# 7_U-FL-Connectors_GND.net
KiCad netlist of a schematic drawn in Altium Designer
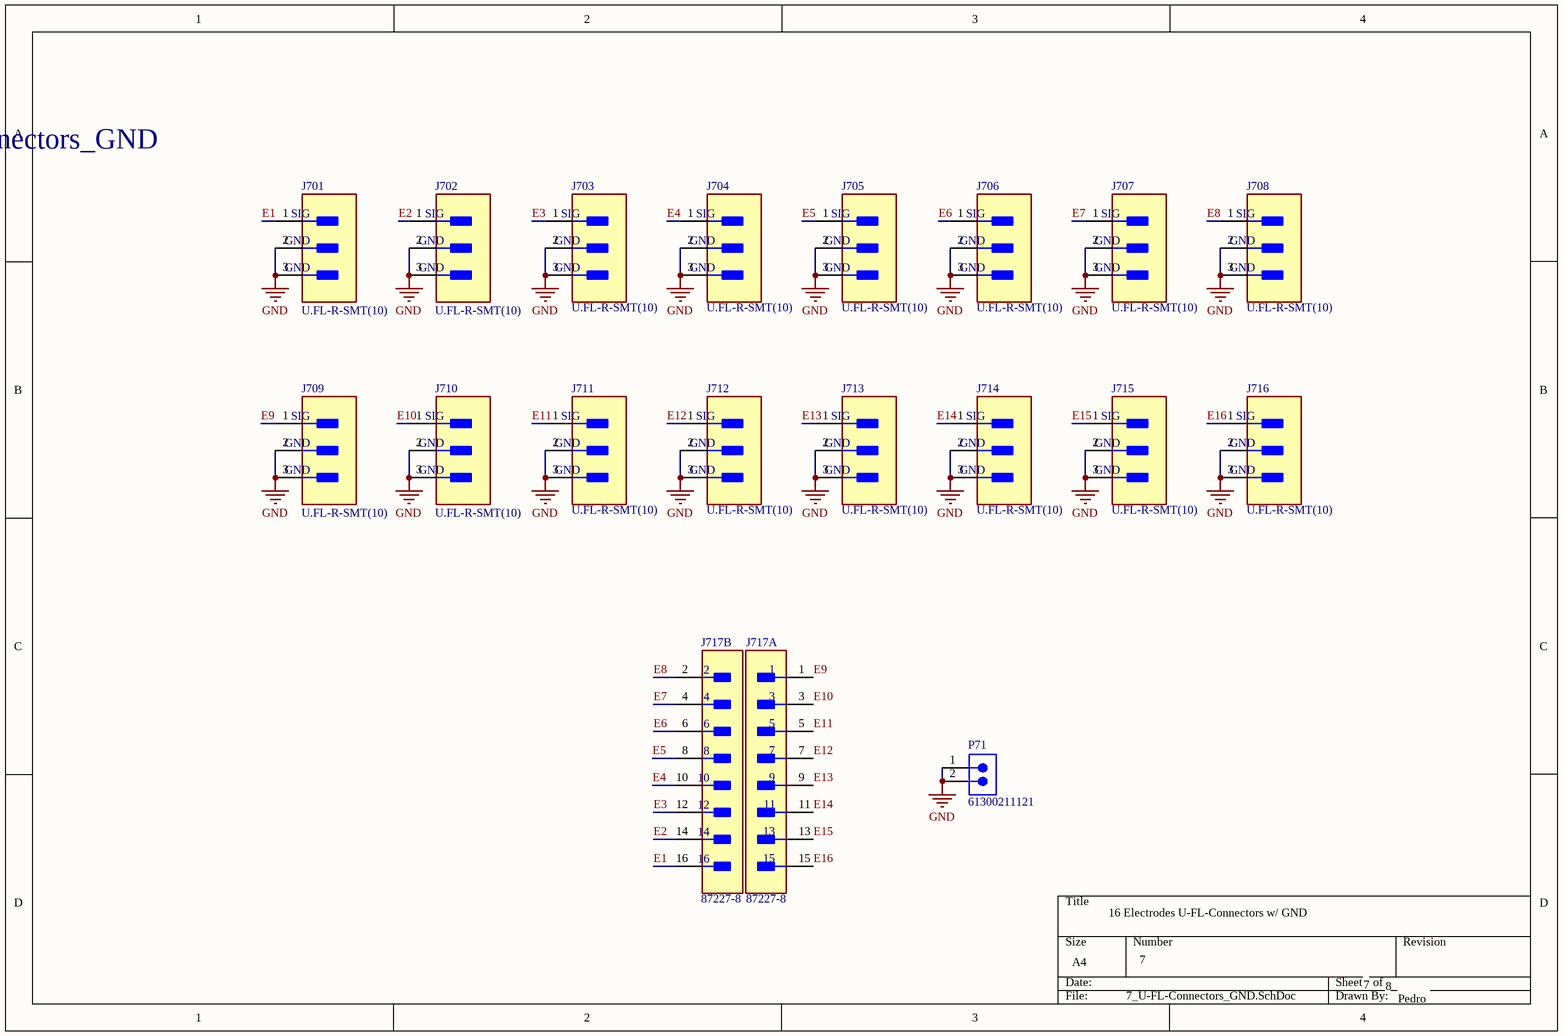
[diagram p0: 7_U-FL-Connectors_GND.SchDoc]

(export (version "E")
  (design (tool "Eeschema 10.0.6"))
  (components
    (comp (ref "J701")
      (value "U.FL-R-SMT(10)")
      (footprint "FP-U_FL-R-SMT_10-MFG")
      (description "CONN U.FL RCPT STR 50 OHM SMD")
      (libsource (lib "RPI_EIT_SchLib") (part "eef6fde44c591823e8076210edfe12f"))
    )
    (comp (ref "J702")
      (value "U.FL-R-SMT(10)")
      (footprint "FP-U_FL-R-SMT_10-MFG")
      (description "CONN U.FL RCPT STR 50 OHM SMD")
      (libsource (lib "RPI_EIT_SchLib") (part "eef6fde44c591823e8076210edfe12f"))
    )
    (comp (ref "J703")
      (value "U.FL-R-SMT(10)")
      (footprint "FP-U_FL-R-SMT_10-MFG")
      (description "CONN U.FL RCPT STR 50 OHM SMD")
      (libsource (lib "RPI_EIT_SchLib") (part "eef6fde44c591823e8076210edfe12f"))
    )
    (comp (ref "J704")
      (value "U.FL-R-SMT(10)")
      (footprint "FP-U_FL-R-SMT_10-MFG")
      (description "CONN U.FL RCPT STR 50 OHM SMD")
      (libsource (lib "RPI_EIT_SchLib") (part "eef6fde44c591823e8076210edfe12f"))
    )
    (comp (ref "J705")
      (value "U.FL-R-SMT(10)")
      (footprint "FP-U_FL-R-SMT_10-MFG")
      (description "CONN U.FL RCPT STR 50 OHM SMD")
      (libsource (lib "RPI_EIT_SchLib") (part "eef6fde44c591823e8076210edfe12f"))
    )
    (comp (ref "J706")
      (value "U.FL-R-SMT(10)")
      (footprint "FP-U_FL-R-SMT_10-MFG")
      (description "CONN U.FL RCPT STR 50 OHM SMD")
      (libsource (lib "RPI_EIT_SchLib") (part "eef6fde44c591823e8076210edfe12f"))
    )
    (comp (ref "J707")
      (value "U.FL-R-SMT(10)")
      (footprint "FP-U_FL-R-SMT_10-MFG")
      (description "CONN U.FL RCPT STR 50 OHM SMD")
      (libsource (lib "RPI_EIT_SchLib") (part "eef6fde44c591823e8076210edfe12f"))
    )
    (comp (ref "J708")
      (value "U.FL-R-SMT(10)")
      (footprint "FP-U_FL-R-SMT_10-MFG")
      (description "CONN U.FL RCPT STR 50 OHM SMD")
      (libsource (lib "RPI_EIT_SchLib") (part "eef6fde44c591823e8076210edfe12f"))
    )
    (comp (ref "J709")
      (value "U.FL-R-SMT(10)")
      (footprint "FP-U_FL-R-SMT_10-MFG")
      (description "CONN U.FL RCPT STR 50 OHM SMD")
      (libsource (lib "RPI_EIT_SchLib") (part "eef6fde44c591823e8076210edfe12f"))
    )
    (comp (ref "J710")
      (value "U.FL-R-SMT(10)")
      (footprint "FP-U_FL-R-SMT_10-MFG")
      (description "CONN U.FL RCPT STR 50 OHM SMD")
      (libsource (lib "RPI_EIT_SchLib") (part "eef6fde44c591823e8076210edfe12f"))
    )
    (comp (ref "J711")
      (value "U.FL-R-SMT(10)")
      (footprint "FP-U_FL-R-SMT_10-MFG")
      (description "CONN U.FL RCPT STR 50 OHM SMD")
      (libsource (lib "RPI_EIT_SchLib") (part "eef6fde44c591823e8076210edfe12f"))
    )
    (comp (ref "J712")
      (value "U.FL-R-SMT(10)")
      (footprint "FP-U_FL-R-SMT_10-MFG")
      (description "CONN U.FL RCPT STR 50 OHM SMD")
      (libsource (lib "RPI_EIT_SchLib") (part "eef6fde44c591823e8076210edfe12f"))
    )
    (comp (ref "J713")
      (value "U.FL-R-SMT(10)")
      (footprint "FP-U_FL-R-SMT_10-MFG")
      (description "CONN U.FL RCPT STR 50 OHM SMD")
      (libsource (lib "RPI_EIT_SchLib") (part "eef6fde44c591823e8076210edfe12f"))
    )
    (comp (ref "J714")
      (value "U.FL-R-SMT(10)")
      (footprint "FP-U_FL-R-SMT_10-MFG")
      (description "CONN U.FL RCPT STR 50 OHM SMD")
      (libsource (lib "RPI_EIT_SchLib") (part "eef6fde44c591823e8076210edfe12f"))
    )
    (comp (ref "J715")
      (value "U.FL-R-SMT(10)")
      (footprint "FP-U_FL-R-SMT_10-MFG")
      (description "CONN U.FL RCPT STR 50 OHM SMD")
      (libsource (lib "RPI_EIT_SchLib") (part "eef6fde44c591823e8076210edfe12f"))
    )
    (comp (ref "J716")
      (value "U.FL-R-SMT(10)")
      (footprint "FP-U_FL-R-SMT_10-MFG")
      (description "CONN U.FL RCPT STR 50 OHM SMD")
      (libsource (lib "RPI_EIT_SchLib") (part "eef6fde44c591823e8076210edfe12f"))
    )
    (comp (ref "J717")
      (value "87227-8")
      (footprint "FP-87227-8-MFG")
      (description "CONN HEADER VERT 16POS 2.54MM")
      (fields
        (field (name "MANUFACTURER") "TE Connectivity")
        (field (name "OCTOPART") "https://octopart.com/87227-8-te+connectivity-39407754")
      )
      (libsource (lib "Altium Content Vault") (part "4b6d22b45e2f925f038cba5d936fbcc"))
    )
    (comp (ref "P71")
      (value "61300211121")
      (footprint "61300211121")
      (libsource (lib "Altium Content Vault") (part "Header_Male_1R_02P"))
    )
  )
  (nets
    (net (code "1") (name "/E1") (class "Default")
      (node (ref "J701") (pin "1") (pinfunction "SIG_1") (pintype "passive"))
      (node (ref "J717") (pin "16") (pinfunction "16_16") (pintype "passive"))
    )
    (net (code "2") (name "/E2") (class "Default")
      (node (ref "J702") (pin "1") (pinfunction "SIG_1") (pintype "passive"))
      (node (ref "J717") (pin "14") (pinfunction "14_14") (pintype "passive"))
    )
    (net (code "3") (name "/E3") (class "Default")
      (node (ref "J703") (pin "1") (pinfunction "SIG_1") (pintype "passive"))
      (node (ref "J717") (pin "12") (pinfunction "12_12") (pintype "passive"))
    )
    (net (code "4") (name "/E4") (class "Default")
      (node (ref "J704") (pin "1") (pinfunction "SIG_1") (pintype "passive"))
      (node (ref "J717") (pin "10") (pinfunction "10_10") (pintype "passive"))
    )
    (net (code "5") (name "/E5") (class "Default")
      (node (ref "J705") (pin "1") (pinfunction "SIG_1") (pintype "passive"))
      (node (ref "J717") (pin "8") (pinfunction "8_8") (pintype "passive"))
    )
    (net (code "6") (name "/E6") (class "Default")
      (node (ref "J706") (pin "1") (pinfunction "SIG_1") (pintype "passive"))
      (node (ref "J717") (pin "6") (pinfunction "6_6") (pintype "passive"))
    )
    (net (code "7") (name "/E7") (class "Default")
      (node (ref "J707") (pin "1") (pinfunction "SIG_1") (pintype "passive"))
      (node (ref "J717") (pin "4") (pinfunction "4_4") (pintype "passive"))
    )
    (net (code "8") (name "/E8") (class "Default")
      (node (ref "J708") (pin "1") (pinfunction "SIG_1") (pintype "passive"))
      (node (ref "J717") (pin "2") (pinfunction "2_2") (pintype "passive"))
    )
    (net (code "9") (name "/E9") (class "Default")
      (node (ref "J709") (pin "1") (pinfunction "SIG_1") (pintype "passive"))
      (node (ref "J717") (pin "1") (pinfunction "1_1") (pintype "passive"))
    )
    (net (code "10") (name "/E10") (class "Default")
      (node (ref "J710") (pin "1") (pinfunction "SIG_1") (pintype "passive"))
      (node (ref "J717") (pin "3") (pinfunction "3_3") (pintype "passive"))
    )
    (net (code "11") (name "/E11") (class "Default")
      (node (ref "J711") (pin "1") (pinfunction "SIG_1") (pintype "passive"))
      (node (ref "J717") (pin "5") (pinfunction "5_5") (pintype "passive"))
    )
    (net (code "12") (name "/E12") (class "Default")
      (node (ref "J712") (pin "1") (pinfunction "SIG_1") (pintype "passive"))
      (node (ref "J717") (pin "7") (pinfunction "7_7") (pintype "passive"))
    )
    (net (code "13") (name "/E13") (class "Default")
      (node (ref "J713") (pin "1") (pinfunction "SIG_1") (pintype "passive"))
      (node (ref "J717") (pin "9") (pinfunction "9_9") (pintype "passive"))
    )
    (net (code "14") (name "/E14") (class "Default")
      (node (ref "J714") (pin "1") (pinfunction "SIG_1") (pintype "passive"))
      (node (ref "J717") (pin "11") (pinfunction "11_11") (pintype "passive"))
    )
    (net (code "15") (name "/E15") (class "Default")
      (node (ref "J715") (pin "1") (pinfunction "SIG_1") (pintype "passive"))
      (node (ref "J717") (pin "13") (pinfunction "13_13") (pintype "passive"))
    )
    (net (code "16") (name "/E16") (class "Default")
      (node (ref "J716") (pin "1") (pinfunction "SIG_1") (pintype "passive"))
      (node (ref "J717") (pin "15") (pinfunction "15_15") (pintype "passive"))
    )
    (net (code "17") (name "GND") (class "Default")
      (node (ref "J701") (pin "2") (pinfunction "GND_2") (pintype "power_in"))
      (node (ref "J701") (pin "3") (pinfunction "GND_3") (pintype "power_in"))
      (node (ref "J702") (pin "2") (pinfunction "GND_2") (pintype "power_in"))
      (node (ref "J702") (pin "3") (pinfunction "GND_3") (pintype "power_in"))
      (node (ref "J703") (pin "2") (pinfunction "GND_2") (pintype "power_in"))
      (node (ref "J703") (pin "3") (pinfunction "GND_3") (pintype "power_in"))
      (node (ref "J704") (pin "2") (pinfunction "GND_2") (pintype "power_in"))
      (node (ref "J704") (pin "3") (pinfunction "GND_3") (pintype "power_in"))
      (node (ref "J705") (pin "2") (pinfunction "GND_2") (pintype "power_in"))
      (node (ref "J705") (pin "3") (pinfunction "GND_3") (pintype "power_in"))
      (node (ref "J706") (pin "2") (pinfunction "GND_2") (pintype "power_in"))
      (node (ref "J706") (pin "3") (pinfunction "GND_3") (pintype "power_in"))
      (node (ref "J707") (pin "2") (pinfunction "GND_2") (pintype "power_in"))
      (node (ref "J707") (pin "3") (pinfunction "GND_3") (pintype "power_in"))
      (node (ref "J708") (pin "2") (pinfunction "GND_2") (pintype "power_in"))
      (node (ref "J708") (pin "3") (pinfunction "GND_3") (pintype "power_in"))
      (node (ref "J709") (pin "2") (pinfunction "GND_2") (pintype "power_in"))
      (node (ref "J709") (pin "3") (pinfunction "GND_3") (pintype "power_in"))
      (node (ref "J710") (pin "2") (pinfunction "GND_2") (pintype "power_in"))
      (node (ref "J710") (pin "3") (pinfunction "GND_3") (pintype "power_in"))
      (node (ref "J711") (pin "2") (pinfunction "GND_2") (pintype "power_in"))
      (node (ref "J711") (pin "3") (pinfunction "GND_3") (pintype "power_in"))
      (node (ref "J712") (pin "2") (pinfunction "GND_2") (pintype "power_in"))
      (node (ref "J712") (pin "3") (pinfunction "GND_3") (pintype "power_in"))
      (node (ref "J713") (pin "2") (pinfunction "GND_2") (pintype "power_in"))
      (node (ref "J713") (pin "3") (pinfunction "GND_3") (pintype "power_in"))
      (node (ref "J714") (pin "2") (pinfunction "GND_2") (pintype "power_in"))
      (node (ref "J714") (pin "3") (pinfunction "GND_3") (pintype "power_in"))
      (node (ref "J715") (pin "2") (pinfunction "GND_2") (pintype "power_in"))
      (node (ref "J715") (pin "3") (pinfunction "GND_3") (pintype "power_in"))
      (node (ref "J716") (pin "2") (pinfunction "GND_2") (pintype "power_in"))
      (node (ref "J716") (pin "3") (pinfunction "GND_3") (pintype "power_in"))
      (node (ref "P71") (pin "1") (pinfunction "1_1") (pintype "passive"))
      (node (ref "P71") (pin "2") (pinfunction "2_2") (pintype "passive"))
    )
  )
)
